# ADG.net
KiCad netlist of a schematic drawn in Altium Designer
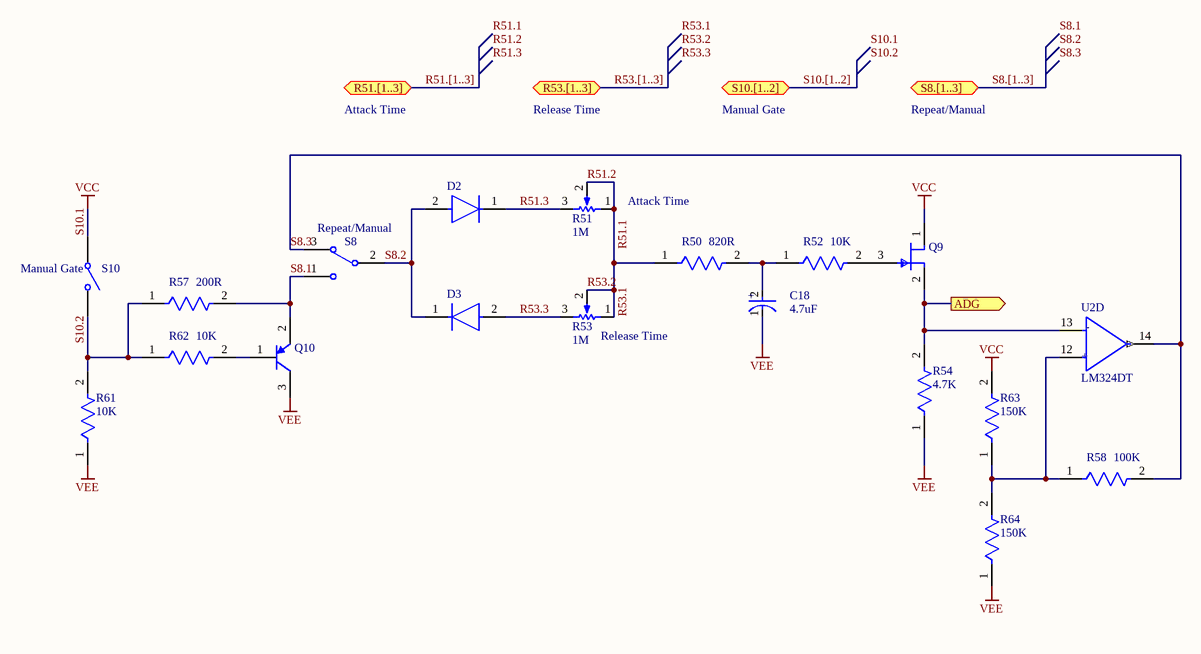
[diagram p0: ADG.SchDoc]

(export (version "E")
  (design (tool "Eeschema 10.0.6"))
  (components
    (comp (ref "C18")
      (value "~")
      (footprint "FP-OS-CON-SMT-A5-MFG")
      (fields
        (field (name "MANUFACTURER") "Wurth Electronics")
        (field (name "MANUFACTURER PART NUMBER") "865080640004")
        (field (name "TOLERANCE") "20%")
        (field (name "CAPACITANCE") "4.7uF")
      )
      (libsource (lib "Altium Content Vault") (part "a00bbbee19879c290e62620ae7e47b1"))
    )
    (comp (ref "D2")
      (value "1N4448WS-7-F")
      (footprint "FP-SOD323-MFG")
      (description "DIODE GEN PURP 75V 250MA SOD323")
      (fields
        (field (name "MANUFACTURER") "Diodes Incorporated")
        (field (name "OCTOPART") "https://octopart.com/1n4448ws-7-f-diodes+inc.-55389585")
      )
      (libsource (lib "Altium Content Vault") (part "d7152d700b627762746794eb795d46e"))
    )
    (comp (ref "D3")
      (value "1N4448WS-7-F")
      (footprint "FP-SOD323-MFG")
      (description "DIODE GEN PURP 75V 250MA SOD323")
      (fields
        (field (name "MANUFACTURER") "Diodes Incorporated")
        (field (name "OCTOPART") "https://octopart.com/1n4448ws-7-f-diodes+inc.-55389585")
      )
      (libsource (lib "Altium Content Vault") (part "d7152d700b627762746794eb795d46e"))
    )
    (comp (ref "Q9")
      (value "MMBFJ113")
      (footprint "FP-318BM-IPC_C")
      (description "JFET N-CH 35V 350MW SOT23")
      (fields
        (field (name "MANUFACTURER") "ON Semiconductor")
        (field (name "OCTOPART") "https://octopart.com/mmbfj113-on+semiconductor-84330253")
      )
      (libsource (lib "Altium Content Vault") (part "14398f7355be6f33287877db3ee21c7"))
    )
    (comp (ref "Q10")
      (value "MMBT3906LT1G")
      (footprint "ONSC-SOT-23-3-318-08_V")
      (description "General Purpose Transistor, PNP Silicon, 3-Pin SOT-23, Pb-Free, Tape and Reel")
      (fields (field (name "MANUFACTURER") "On Semiconductor"))
      (libsource (lib "Altium Content Vault") (part "ONSC-PNP-B1E2C3-3"))
    )
    (comp (ref "R50")
      (value "ESR03EZPJ821")
      (footprint "FP-ESR03-IPC_B")
      (description "820Ω ±5% 0.25W 0603 Anti-Surge Chip Resistor AEC-Q200")
      (fields (field (name "TOLERANCE") "5%") (field (name "RESISTANCE") "820R"))
      (libsource (lib "Altium Content Vault") (part "1029c3af85768c4190bb7ad29bc67b5"))
    )
    (comp (ref "R51")
      (value "Attack Time")
      (footprint "VR5")
      (description "Potentiometer")
      (fields (field (name "ALTIUM_VALUE") "1M") (field (name "PUBLISHER") "Altium Limited"))
      (libsource (lib "Miscellaneous Devices") (part "RPot"))
    )
    (comp (ref "R52")
      (value "ESR03EZPJ103")
      (footprint "FP-ESR03-IPC_B")
      (description "10kΩ ±5% 0.25W 0603 Anti-Surge Chip Resistor AEC-Q200")
      (fields (field (name "TOLERANCE") "5%") (field (name "RESISTANCE") "10K"))
      (libsource (lib "Altium Content Vault") (part "1029c3af85768c4190bb7ad29bc67b5"))
    )
    (comp (ref "R53")
      (value "Release Time")
      (footprint "VR5")
      (description "Potentiometer")
      (fields (field (name "ALTIUM_VALUE") "1M") (field (name "PUBLISHER") "Altium Limited"))
      (libsource (lib "Miscellaneous Devices") (part "RPot"))
    )
    (comp (ref "R54")
      (value "ESR03EZPJ472")
      (footprint "FP-ESR03-IPC_B")
      (description "4.7kΩ ±5% 0.25W 0603 Anti-Surge Chip Resistor AEC-Q200")
      (fields (field (name "TOLERANCE") "5%") (field (name "RESISTANCE") "4.7K"))
      (libsource (lib "Altium Content Vault") (part "1029c3af85768c4190bb7ad29bc67b5"))
    )
    (comp (ref "R57")
      (value "ESR03EZPJ201")
      (footprint "FP-ESR03-IPC_B")
      (description "200Ω ±5% 0.25W 0603 Anti-Surge Chip Resistor AEC-Q200")
      (fields (field (name "RESISTANCE") "200R") (field (name "TOLERANCE") "5%"))
      (libsource (lib "Altium Content Vault") (part "1029c3af85768c4190bb7ad29bc67b5"))
    )
    (comp (ref "R58")
      (value "ESR03EZPJ104")
      (footprint "FP-ESR03-IPC_B")
      (description "100kΩ ±5% 0.25W 0603 Anti-Surge Chip Resistor AEC-Q200")
      (fields (field (name "TOLERANCE") "5%") (field (name "RESISTANCE") "100K"))
      (libsource (lib "Altium Content Vault") (part "1029c3af85768c4190bb7ad29bc67b5"))
    )
    (comp (ref "R61")
      (value "ESR03EZPJ103")
      (footprint "FP-ESR03-IPC_B")
      (description "10kΩ ±5% 0.25W 0603 Anti-Surge Chip Resistor AEC-Q200")
      (fields (field (name "TOLERANCE") "5%") (field (name "RESISTANCE") "10K"))
      (libsource (lib "Altium Content Vault") (part "1029c3af85768c4190bb7ad29bc67b5"))
    )
    (comp (ref "R62")
      (value "ESR03EZPJ103")
      (footprint "FP-ESR03-IPC_B")
      (description "10kΩ ±5% 0.25W 0603 Anti-Surge Chip Resistor AEC-Q200")
      (fields (field (name "TOLERANCE") "5%") (field (name "RESISTANCE") "10K"))
      (libsource (lib "Altium Content Vault") (part "1029c3af85768c4190bb7ad29bc67b5"))
    )
    (comp (ref "R63")
      (value "ESR03EZPJ154")
      (footprint "FP-ESR03-IPC_B")
      (description "150kΩ ±5% 0.25W 0603 Anti-Surge Chip Resistor AEC-Q200")
      (fields (field (name "TOLERANCE") "5%") (field (name "RESISTANCE") "150K"))
      (libsource (lib "Altium Content Vault") (part "1029c3af85768c4190bb7ad29bc67b5"))
    )
    (comp (ref "R64")
      (value "ESR03EZPJ154")
      (footprint "FP-ESR03-IPC_B")
      (description "150kΩ ±5% 0.25W 0603 Anti-Surge Chip Resistor AEC-Q200")
      (fields (field (name "TOLERANCE") "5%") (field (name "RESISTANCE") "150K"))
      (libsource (lib "Altium Content Vault") (part "1029c3af85768c4190bb7ad29bc67b5"))
    )
    (comp (ref "S8")
      (value "Repeat/Manual")
      (footprint "HDR1X3")
      (description "Switch Toggle ON None ON SPDT Round Lever Solder Lug 5A 250VAC 28VDC Panel Mount with Threads")
      (fields
        (field (name "MANUFACTURER") "E-Switch")
        (field (name "MANUFACTURER PART NUMBER") "100SP1T1B1M1QEH")
      )
      (libsource (lib "Miscellaneous Devices") (part "SW-SPDT"))
    )
    (comp (ref "S10")
      (value "Manual Gate")
      (footprint "HDR1X2")
      (description "Pushbutton Switch, SPST-NO, OFF-(ON), Round Red Cap, 3A, 125VAC, Solder, PS1024 Series")
      (fields (field (name "MANUFACTURER") "E-Switch") (field (name "MANUFACTURER PART NUMBER") "PS1024ARED"))
      (libsource (lib "Miscellaneous Devices") (part "SW-SPST"))
    )
    (comp (ref "U2")
      (value "LM324DT")
      (footprint "FP-SO-14-MFG")
      (description "IC OPAMP GP 4 CIRCUIT 14SO")
      (fields
        (field (name "OCTOPART") "https://octopart.com/lm324dt-stmicroelectronics-39579146")
        (field (name "MANUFACTURER") "STMicroelectronics")
      )
      (libsource (lib "Altium Content Vault") (part "a065ef67e5aa9ef3942d43d6008d043"))
    )
  )
  (nets
    (net (code "1") (name "/ADG") (class "Default")
      (node (ref "Q9") (pin "2") (pinfunction "S_2") (pintype "passive"))
      (node (ref "R54") (pin "2") (pinfunction "2_2") (pintype "passive"))
      (node (ref "U2") (pin "13") (pinfunction "Inverting_Input_4_13") (pintype "tri_state"))
    )
    (net (code "2") (name "/R51.2") (class "Default")
      (node (ref "R50") (pin "1") (pinfunction "1_1") (pintype "passive"))
      (node (ref "R51") (pin "1") (pinfunction "TOP_1") (pintype "passive"))
      (node (ref "R51") (pin "2") (pinfunction "TAP_2") (pintype "passive"))
      (node (ref "R53") (pin "1") (pinfunction "TOP_1") (pintype "passive"))
      (node (ref "R53") (pin "2") (pinfunction "TAP_2") (pintype "passive"))
    )
    (net (code "3") (name "/R51.3") (class "Default")
      (node (ref "D2") (pin "1") (pinfunction "C_1") (pintype "passive"))
      (node (ref "R51") (pin "3") (pinfunction "BOT_3") (pintype "passive"))
    )
    (net (code "5") (name "/R53.3") (class "Default")
      (node (ref "D3") (pin "2") (pinfunction "A_2") (pintype "passive"))
      (node (ref "R53") (pin "3") (pinfunction "BOT_3") (pintype "passive"))
    )
    (net (code "7") (name "/S8.1") (class "Default")
      (node (ref "Q10") (pin "2") (pinfunction "E_2") (pintype "passive"))
      (node (ref "R57") (pin "2") (pinfunction "2_2") (pintype "passive"))
      (node (ref "S8") (pin "1") (pinfunction "1_1") (pintype "passive"))
    )
    (net (code "8") (name "/S8.2") (class "Default")
      (node (ref "D2") (pin "2") (pinfunction "A_2") (pintype "passive"))
      (node (ref "D3") (pin "1") (pinfunction "C_1") (pintype "passive"))
      (node (ref "S8") (pin "2") (pinfunction "2_2") (pintype "passive"))
    )
    (net (code "9") (name "/S8.3") (class "Default")
      (node (ref "R58") (pin "2") (pinfunction "2_2") (pintype "passive"))
      (node (ref "S8") (pin "3") (pinfunction "3_3") (pintype "passive"))
      (node (ref "U2") (pin "14") (pinfunction "Output_4_14") (pintype "output"))
    )
    (net (code "11") (name "/S10.2") (class "Default")
      (node (ref "R57") (pin "1") (pinfunction "1_1") (pintype "passive"))
      (node (ref "R61") (pin "2") (pinfunction "2_2") (pintype "passive"))
      (node (ref "R62") (pin "1") (pinfunction "1_1") (pintype "passive"))
      (node (ref "S10") (pin "2") (pinfunction "NO_2") (pintype "passive"))
    )
    (net (code "13") (name "Net-(C18-A)") (class "Default")
      (node (ref "C18") (pin "2") (pinfunction "A_2") (pintype "passive"))
      (node (ref "R50") (pin "2") (pinfunction "2_2") (pintype "passive"))
      (node (ref "R52") (pin "1") (pinfunction "1_1") (pintype "passive"))
    )
    (net (code "14") (name "Net-(Q9-G)") (class "Default")
      (node (ref "Q9") (pin "3") (pinfunction "G_3") (pintype "passive"))
      (node (ref "R52") (pin "2") (pinfunction "2_2") (pintype "passive"))
    )
    (net (code "15") (name "Net-(Q10-B)") (class "Default")
      (node (ref "Q10") (pin "1") (pinfunction "B_1") (pintype "passive"))
      (node (ref "R62") (pin "2") (pinfunction "2_2") (pintype "passive"))
    )
    (net (code "16") (name "Net-(U2D-Non-Inverting_Input_4)") (class "Default")
      (node (ref "R58") (pin "1") (pinfunction "1_1") (pintype "passive"))
      (node (ref "R63") (pin "1") (pinfunction "1_1") (pintype "passive"))
      (node (ref "R64") (pin "2") (pinfunction "2_2") (pintype "passive"))
      (node (ref "U2") (pin "12") (pinfunction "Non-Inverting_Input_4_12") (pintype "tri_state"))
    )
    (net (code "17") (name "VCC") (class "Default")
      (node (ref "Q9") (pin "1") (pinfunction "D_1") (pintype "passive"))
      (node (ref "R63") (pin "2") (pinfunction "2_2") (pintype "passive"))
      (node (ref "S10") (pin "1") (pinfunction "COMMON_1") (pintype "passive"))
    )
    (net (code "18") (name "VEE") (class "Default")
      (node (ref "C18") (pin "1") (pinfunction "C_1") (pintype "passive"))
      (node (ref "Q10") (pin "3") (pinfunction "C_3") (pintype "passive"))
      (node (ref "R54") (pin "1") (pinfunction "1_1") (pintype "passive"))
      (node (ref "R61") (pin "1") (pinfunction "1_1") (pintype "passive"))
      (node (ref "R64") (pin "1") (pinfunction "1_1") (pintype "passive"))
    )
  )
)
